# Sonde.net
KiCad netlist of a schematic drawn in EAGLE
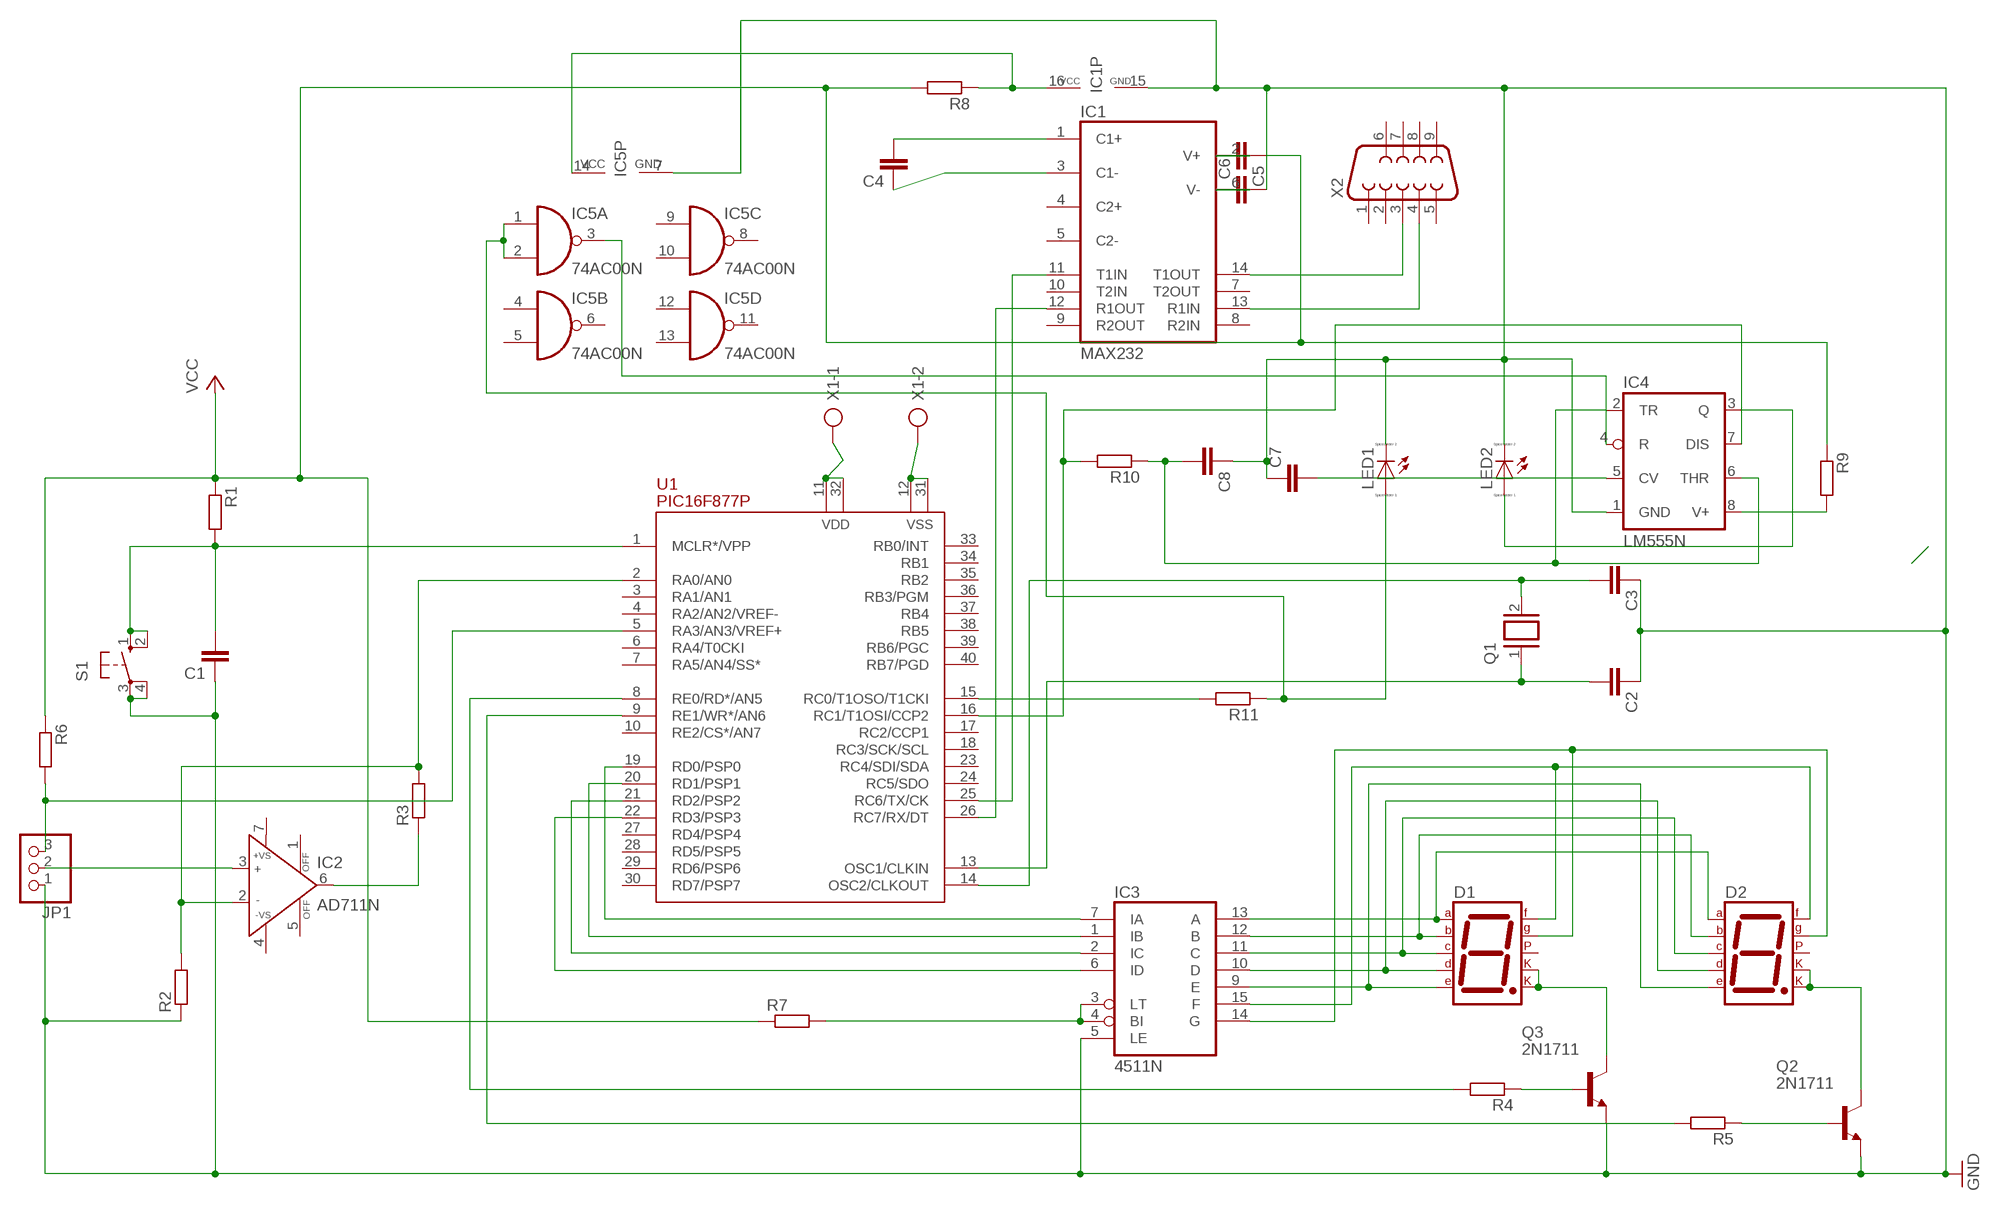
[diagram p0: schematic, sheet 1]

(export (version "E")
  (design (tool "Eeschema 10.0.6"))
  (components
    (comp (ref "C1")
      (value "C-EU025-024X044")
      (footprint "eagle-import:C025-024X044")
      (libsource (lib "eagle-import") (part "C-EU025-024X044"))
    )
    (comp (ref "C2")
      (value "C-EU025-024X044")
      (footprint "eagle-import:C025-024X044")
      (libsource (lib "eagle-import") (part "C-EU025-024X044"))
    )
    (comp (ref "C3")
      (value "C-EU025-024X044")
      (footprint "eagle-import:C025-024X044")
      (libsource (lib "eagle-import") (part "C-EU025-024X044"))
    )
    (comp (ref "C4")
      (value "C-EU025-024X044")
      (footprint "eagle-import:C025-024X044")
      (libsource (lib "eagle-import") (part "C-EU025-024X044"))
    )
    (comp (ref "C5")
      (value "C-EU025-024X044")
      (footprint "eagle-import:C025-024X044")
      (libsource (lib "eagle-import") (part "C-EU025-024X044"))
    )
    (comp (ref "C6")
      (value "C-EU025-024X044")
      (footprint "eagle-import:C025-024X044")
      (libsource (lib "eagle-import") (part "C-EU025-024X044"))
    )
    (comp (ref "C7")
      (value "C-EU025-024X044")
      (footprint "eagle-import:C025-024X044")
      (libsource (lib "eagle-import") (part "C-EU025-024X044"))
    )
    (comp (ref "C8")
      (value "C-EU025-024X044")
      (footprint "eagle-import:C025-024X044")
      (libsource (lib "eagle-import") (part "C-EU025-024X044"))
    )
    (comp (ref "D1")
      (value "7SEG-CK")
      (footprint "eagle-import:7SEG-13")
      (libsource (lib "eagle-import") (part "7SEG-CK"))
    )
    (comp (ref "D2")
      (value "7SEG-CK")
      (footprint "eagle-import:7SEG-13")
      (libsource (lib "eagle-import") (part "7SEG-CK"))
    )
    (comp (ref "IC1")
      (value "MAX232")
      (footprint "eagle-import:DIL16")
      (fields (field (name "MF") "MAXIM") (field (name "MPN") "MAX232ACPE+"))
      (libsource (lib "eagle-import") (part "MAX232"))
    )
    (comp (ref "IC2")
      (value "AD711N")
      (footprint "eagle-import:DIL08")
      (fields (field (name "MPN") "AD711BQ"))
      (libsource (lib "eagle-import") (part "AD711N"))
    )
    (comp (ref "IC3")
      (value "4511N")
      (footprint "eagle-import:DIL16")
      (libsource (lib "eagle-import") (part "4511N"))
    )
    (comp (ref "IC4")
      (value "LM555N")
      (footprint "eagle-import:DIL08")
      (libsource (lib "eagle-import") (part "555NLM"))
    )
    (comp (ref "IC5")
      (value "74AC00N")
      (footprint "eagle-import:DIL14")
      (libsource (lib "eagle-import") (part "7400NAC"))
    )
    (comp (ref "JP1")
      (value "PINHD-1X3")
      (footprint "eagle-import:1X03")
      (libsource (lib "eagle-import") (part "PINHD-1X3"))
    )
    (comp (ref "LED1")
      (value "LED_ELD260")
      (footprint "eagle-import:LED_LD260")
      (libsource (lib "eagle-import") (part "LED_ELD260"))
    )
    (comp (ref "LED2")
      (value "LED_ELD260")
      (footprint "eagle-import:LED_LD260")
      (libsource (lib "eagle-import") (part "LED_ELD260"))
    )
    (comp (ref "Q1")
      (value "XTAL/S")
      (footprint "eagle-import:QS")
      (libsource (lib "eagle-import") (part "XTAL/S"))
    )
    (comp (ref "Q2")
      (value "2N1711")
      (footprint "eagle-import:TO39")
      (libsource (lib "eagle-import") (part "2N1711"))
    )
    (comp (ref "Q3")
      (value "2N1711")
      (footprint "eagle-import:TO39")
      (libsource (lib "eagle-import") (part "2N1711"))
    )
    (comp (ref "R1")
      (value "R-EU_0207/10")
      (footprint "eagle-import:0207_10")
      (libsource (lib "eagle-import") (part "R-EU_0207/10"))
    )
    (comp (ref "R2")
      (value "R-EU_0207/10")
      (footprint "eagle-import:0207_10")
      (libsource (lib "eagle-import") (part "R-EU_0207/10"))
    )
    (comp (ref "R3")
      (value "R-EU_0207/10")
      (footprint "eagle-import:0207_10")
      (libsource (lib "eagle-import") (part "R-EU_0207/10"))
    )
    (comp (ref "R4")
      (value "R-EU_0207/10")
      (footprint "eagle-import:0207_10")
      (libsource (lib "eagle-import") (part "R-EU_0207/10"))
    )
    (comp (ref "R5")
      (value "R-EU_0207/10")
      (footprint "eagle-import:0207_10")
      (libsource (lib "eagle-import") (part "R-EU_0207/10"))
    )
    (comp (ref "R6")
      (value "R-EU_0207/10")
      (footprint "eagle-import:0207_10")
      (libsource (lib "eagle-import") (part "R-EU_0207/10"))
    )
    (comp (ref "R7")
      (value "R-EU_0207/10")
      (footprint "eagle-import:0207_10")
      (libsource (lib "eagle-import") (part "R-EU_0207/10"))
    )
    (comp (ref "R8")
      (value "R-EU_0207/10")
      (footprint "eagle-import:0207_10")
      (libsource (lib "eagle-import") (part "R-EU_0207/10"))
    )
    (comp (ref "R9")
      (value "R-EU_0207/10")
      (footprint "eagle-import:0207_10")
      (libsource (lib "eagle-import") (part "R-EU_0207/10"))
    )
    (comp (ref "R10")
      (value "R-EU_0207/10")
      (footprint "eagle-import:0207_10")
      (libsource (lib "eagle-import") (part "R-EU_0207/10"))
    )
    (comp (ref "R11")
      (value "R-EU_0207/10")
      (footprint "eagle-import:0207_10")
      (libsource (lib "eagle-import") (part "R-EU_0207/10"))
    )
    (comp (ref "S1")
      (value "10-XX")
      (footprint "eagle-import:B3F-10XX")
      (fields (field (name "MPN") "B3F-1000"))
      (libsource (lib "eagle-import") (part "10-XX"))
    )
    (comp (ref "U1")
      (value "PIC16F877P")
      (footprint "eagle-import:DIL40")
      (libsource (lib "eagle-import") (part "PIC16F877P"))
    )
    (comp (ref "X1")
      (value "AK300/2")
      (footprint "eagle-import:AK300_2")
      (libsource (lib "eagle-import") (part "AK300/2"))
    )
    (comp (ref "X2")
      (value "F09D")
      (footprint "eagle-import:F09D")
      (libsource (lib "eagle-import") (part "F09D"))
    )
  )
  (nets
    (net (code "1") (name "GND") (class "Default")
      (node (ref "C1") (pin "1") (pinfunction "1_1") (pintype "passive"))
      (node (ref "C2") (pin "1") (pinfunction "1_1") (pintype "passive"))
      (node (ref "C3") (pin "1") (pinfunction "1_1") (pintype "passive"))
      (node (ref "C6") (pin "2") (pinfunction "2_2") (pintype "passive"))
      (node (ref "C7") (pin "1") (pinfunction "1_1") (pintype "passive"))
      (node (ref "C8") (pin "1") (pinfunction "1_1") (pintype "passive"))
      (node (ref "IC1") (pin "15") (pinfunction "GND_15") (pintype "power_in"))
      (node (ref "IC3") (pin "5") (pinfunction "LE_5") (pintype "input"))
      (node (ref "IC4") (pin "1") (pinfunction "GND_1") (pintype "power_in"))
      (node (ref "IC5") (pin "7") (pinfunction "GND_7") (pintype "power_in"))
      (node (ref "JP1") (pin "1") (pinfunction "1_1") (pintype "passive"))
      (node (ref "LED1") (pin "K") (pinfunction "C_K") (pintype "passive"))
      (node (ref "LED2") (pin "K") (pinfunction "C_K") (pintype "passive"))
      (node (ref "Q2") (pin "1") (pinfunction "E_1") (pintype "passive"))
      (node (ref "Q3") (pin "1") (pinfunction "E_1") (pintype "passive"))
      (node (ref "R2") (pin "1") (pinfunction "1_1") (pintype "passive"))
      (node (ref "S1") (pin "3") (pinfunction "P_3") (pintype "passive"))
      (node (ref "S1") (pin "4") (pinfunction "P1_4") (pintype "passive"))
    )
    (net (code "2") (name "Net-(D1-A)") (class "Default")
      (node (ref "D1") (pin "7") (pinfunction "A_7") (pintype "passive"))
      (node (ref "D2") (pin "7") (pinfunction "A_7") (pintype "passive"))
      (node (ref "IC3") (pin "13") (pinfunction "A_13") (pintype "output"))
    )
    (net (code "3") (name "Net-(D1-B)") (class "Default")
      (node (ref "D1") (pin "6") (pinfunction "B_6") (pintype "passive"))
      (node (ref "D2") (pin "6") (pinfunction "B_6") (pintype "passive"))
      (node (ref "IC3") (pin "12") (pinfunction "B_12") (pintype "output"))
    )
    (net (code "4") (name "Net-(D1-C)") (class "Default")
      (node (ref "D1") (pin "4") (pinfunction "C_4") (pintype "passive"))
      (node (ref "D2") (pin "4") (pinfunction "C_4") (pintype "passive"))
      (node (ref "IC3") (pin "11") (pinfunction "C_11") (pintype "output"))
    )
    (net (code "5") (name "Net-(D1-CK1)") (class "Default")
      (node (ref "D1") (pin "3") (pinfunction "CK1_3") (pintype "passive"))
      (node (ref "D1") (pin "8") (pinfunction "CK2_8") (pintype "passive"))
      (node (ref "Q3") (pin "3") (pinfunction "C_3") (pintype "passive"))
    )
    (net (code "6") (name "Net-(D1-D)") (class "Default")
      (node (ref "D1") (pin "2") (pinfunction "D_2") (pintype "passive"))
      (node (ref "D2") (pin "2") (pinfunction "D_2") (pintype "passive"))
      (node (ref "IC3") (pin "10") (pinfunction "D_10") (pintype "output"))
    )
    (net (code "7") (name "Net-(D1-E)") (class "Default")
      (node (ref "D1") (pin "1") (pinfunction "E_1") (pintype "passive"))
      (node (ref "D2") (pin "1") (pinfunction "E_1") (pintype "passive"))
      (node (ref "IC3") (pin "9") (pinfunction "E_9") (pintype "output"))
    )
    (net (code "8") (name "Net-(D1-F)") (class "Default")
      (node (ref "D1") (pin "9") (pinfunction "F_9") (pintype "passive"))
      (node (ref "D2") (pin "9") (pinfunction "F_9") (pintype "passive"))
      (node (ref "IC3") (pin "15") (pinfunction "F_15") (pintype "output"))
    )
    (net (code "9") (name "Net-(D1-G)") (class "Default")
      (node (ref "D1") (pin "10") (pinfunction "G_10") (pintype "passive"))
      (node (ref "D2") (pin "10") (pinfunction "G_10") (pintype "passive"))
      (node (ref "IC3") (pin "14") (pinfunction "G_14") (pintype "output"))
    )
    (net (code "10") (name "Net-(D2-CK1)") (class "Default")
      (node (ref "D2") (pin "3") (pinfunction "CK1_3") (pintype "passive"))
      (node (ref "D2") (pin "8") (pinfunction "CK2_8") (pintype "passive"))
      (node (ref "Q2") (pin "3") (pinfunction "C_3") (pintype "passive"))
    )
    (net (code "11") (name "Net-(IC1A-C1+)") (class "Default")
      (node (ref "C4") (pin "2") (pinfunction "2_2") (pintype "passive"))
      (node (ref "IC1") (pin "1") (pinfunction "C1+_1") (pintype "bidirectional"))
    )
    (net (code "12") (name "Net-(IC1A-C1-)") (class "Default")
      (node (ref "C4") (pin "1") (pinfunction "1_1") (pintype "passive"))
      (node (ref "IC1") (pin "3") (pinfunction "C1-_3") (pintype "bidirectional"))
    )
    (net (code "13") (name "Net-(IC1A-R1IN)") (class "Default")
      (node (ref "IC1") (pin "13") (pinfunction "R1IN_13") (pintype "input"))
      (node (ref "X2") (pin "4") (pinfunction "4_4") (pintype "passive"))
    )
    (net (code "14") (name "Net-(IC1A-R1OUT)") (class "Default")
      (node (ref "IC1") (pin "12") (pinfunction "R1OUT_12") (pintype "output"))
      (node (ref "U1") (pin "26") (pinfunction "RC7/RX/DT_26") (pintype "bidirectional"))
    )
    (net (code "15") (name "Net-(IC1A-T1IN)") (class "Default")
      (node (ref "IC1") (pin "11") (pinfunction "T1IN_11") (pintype "input"))
      (node (ref "U1") (pin "25") (pinfunction "RC6/TX/CK_25") (pintype "bidirectional"))
    )
    (net (code "16") (name "Net-(IC1A-T1OUT)") (class "Default")
      (node (ref "IC1") (pin "14") (pinfunction "T1OUT_14") (pintype "output"))
      (node (ref "X2") (pin "3") (pinfunction "3_3") (pintype "passive"))
    )
    (net (code "17") (name "Net-(IC1A-V+)") (class "Default")
      (node (ref "C5") (pin "2") (pinfunction "2_2") (pintype "passive"))
      (node (ref "IC1") (pin "2") (pinfunction "V+_2") (pintype "bidirectional"))
    )
    (net (code "18") (name "Net-(IC1A-V-)") (class "Default")
      (node (ref "C6") (pin "1") (pinfunction "1_1") (pintype "passive"))
      (node (ref "IC1") (pin "6") (pinfunction "V-_6") (pintype "bidirectional"))
    )
    (net (code "19") (name "Net-(IC1B-VCC)") (class "Default")
      (node (ref "IC1") (pin "16") (pinfunction "VCC_16") (pintype "power_in"))
      (node (ref "IC5") (pin "14") (pinfunction "VCC_14") (pintype "power_in"))
      (node (ref "R8") (pin "1") (pinfunction "1_1") (pintype "passive"))
    )
    (net (code "20") (name "Net-(IC2-IN+)") (class "Default")
      (node (ref "IC2") (pin "3") (pinfunction "IN+_3") (pintype "input"))
      (node (ref "JP1") (pin "2") (pinfunction "2_2") (pintype "passive"))
    )
    (net (code "21") (name "Net-(IC2-IN-)") (class "Default")
      (node (ref "IC2") (pin "2") (pinfunction "IN-_2") (pintype "input"))
      (node (ref "R2") (pin "2") (pinfunction "2_2") (pintype "passive"))
      (node (ref "R3") (pin "2") (pinfunction "2_2") (pintype "passive"))
      (node (ref "U1") (pin "2") (pinfunction "RA0/AN0_2") (pintype "bidirectional"))
    )
    (net (code "22") (name "Net-(IC2-OUT)") (class "Default")
      (node (ref "IC2") (pin "6") (pinfunction "OUT_6") (pintype "output"))
      (node (ref "R3") (pin "1") (pinfunction "1_1") (pintype "passive"))
    )
    (net (code "23") (name "Net-(IC3A-BI)") (class "Default")
      (node (ref "IC3") (pin "3") (pinfunction "LT_3") (pintype "input"))
      (node (ref "IC3") (pin "4") (pinfunction "BI_4") (pintype "input"))
      (node (ref "R7") (pin "2") (pinfunction "2_2") (pintype "passive"))
    )
    (net (code "24") (name "Net-(IC3A-IA)") (class "Default")
      (node (ref "IC3") (pin "7") (pinfunction "IA_7") (pintype "input"))
      (node (ref "U1") (pin "19") (pinfunction "RD0/PSP0_19") (pintype "bidirectional"))
    )
    (net (code "25") (name "Net-(IC3A-IB)") (class "Default")
      (node (ref "IC3") (pin "1") (pinfunction "IB_1") (pintype "input"))
      (node (ref "U1") (pin "20") (pinfunction "RD1/PSP1_20") (pintype "bidirectional"))
    )
    (net (code "26") (name "Net-(IC3A-IC)") (class "Default")
      (node (ref "IC3") (pin "2") (pinfunction "IC_2") (pintype "input"))
      (node (ref "U1") (pin "21") (pinfunction "RD2/PSP2_21") (pintype "bidirectional"))
    )
    (net (code "27") (name "Net-(IC3A-ID)") (class "Default")
      (node (ref "IC3") (pin "6") (pinfunction "ID_6") (pintype "input"))
      (node (ref "U1") (pin "22") (pinfunction "RD3/PSP3_22") (pintype "bidirectional"))
    )
    (net (code "28") (name "Net-(IC4-CV)") (class "Default")
      (node (ref "C7") (pin "2") (pinfunction "2_2") (pintype "passive"))
      (node (ref "IC4") (pin "5") (pinfunction "CV_5") (pintype "input"))
    )
    (net (code "29") (name "Net-(IC4-DIS)") (class "Default")
      (node (ref "IC4") (pin "7") (pinfunction "DIS_7") (pintype "input"))
      (node (ref "R10") (pin "2") (pinfunction "2_2") (pintype "passive"))
      (node (ref "U1") (pin "16") (pinfunction "RC1/T1OSI/CCP2_16") (pintype "bidirectional"))
    )
    (net (code "30") (name "Net-(IC4-Q)") (class "Default")
      (node (ref "IC4") (pin "3") (pinfunction "Q_3") (pintype "output"))
      (node (ref "LED2") (pin "A") (pinfunction "A_A") (pintype "passive"))
    )
    (net (code "31") (name "Net-(IC4-R)") (class "Default")
      (node (ref "IC4") (pin "4") (pinfunction "R_4") (pintype "input"))
      (node (ref "IC5") (pin "3") (pinfunction "O_3") (pintype "output"))
    )
    (net (code "32") (name "Net-(IC4-THR)") (class "Default")
      (node (ref "C8") (pin "2") (pinfunction "2_2") (pintype "passive"))
      (node (ref "IC4") (pin "2") (pinfunction "TR_2") (pintype "input"))
      (node (ref "IC4") (pin "6") (pinfunction "THR_6") (pintype "input"))
      (node (ref "R10") (pin "1") (pinfunction "1_1") (pintype "passive"))
    )
    (net (code "33") (name "Net-(IC4-V+)") (class "Default")
      (node (ref "IC4") (pin "8") (pinfunction "V+_8") (pintype "power_in"))
      (node (ref "R9") (pin "2") (pinfunction "2_2") (pintype "passive"))
    )
    (net (code "34") (name "Net-(IC5A-I0)") (class "Default")
      (node (ref "IC5") (pin "1") (pinfunction "I0_1") (pintype "input"))
      (node (ref "IC5") (pin "2") (pinfunction "I1_2") (pintype "input"))
      (node (ref "LED1") (pin "A") (pinfunction "A_A") (pintype "passive"))
      (node (ref "R11") (pin "1") (pinfunction "1_1") (pintype "passive"))
    )
    (net (code "35") (name "Net-(Q2-B)") (class "Default")
      (node (ref "Q2") (pin "2") (pinfunction "B_2") (pintype "passive"))
      (node (ref "R5") (pin "1") (pinfunction "1_1") (pintype "passive"))
    )
    (net (code "36") (name "Net-(Q3-B)") (class "Default")
      (node (ref "Q3") (pin "2") (pinfunction "B_2") (pintype "passive"))
      (node (ref "R4") (pin "1") (pinfunction "1_1") (pintype "passive"))
    )
    (net (code "37") (name "Net-(S1-S)") (class "Default")
      (node (ref "C1") (pin "2") (pinfunction "2_2") (pintype "passive"))
      (node (ref "R1") (pin "2") (pinfunction "2_2") (pintype "passive"))
      (node (ref "S1") (pin "1") (pinfunction "S_1") (pintype "passive"))
      (node (ref "S1") (pin "2") (pinfunction "S1_2") (pintype "passive"))
      (node (ref "U1") (pin "1") (pinfunction "MCLR*/VPP_1") (pintype "input"))
    )
    (net (code "38") (name "Net-(U1-OSC1{slash}CLKIN)") (class "Default")
      (node (ref "C2") (pin "2") (pinfunction "2_2") (pintype "passive"))
      (node (ref "Q1") (pin "1") (pinfunction "1_1") (pintype "passive"))
      (node (ref "U1") (pin "13") (pinfunction "OSC1/CLKIN_13") (pintype "input"))
    )
    (net (code "39") (name "Net-(U1-OSC2{slash}CLKOUT)") (class "Default")
      (node (ref "C3") (pin "2") (pinfunction "2_2") (pintype "passive"))
      (node (ref "Q1") (pin "2") (pinfunction "2_2") (pintype "passive"))
      (node (ref "U1") (pin "14") (pinfunction "OSC2/CLKOUT_14") (pintype "output"))
    )
    (net (code "40") (name "Net-(U1-RA3{slash}AN3{slash}VREF+)") (class "Default")
      (node (ref "JP1") (pin "3") (pinfunction "3_3") (pintype "passive"))
      (node (ref "R6") (pin "2") (pinfunction "2_2") (pintype "passive"))
      (node (ref "U1") (pin "5") (pinfunction "RA3/AN3/VREF+_5") (pintype "bidirectional"))
    )
    (net (code "41") (name "Net-(U1-RC0{slash}T1OSO{slash}T1CKI)") (class "Default")
      (node (ref "R11") (pin "2") (pinfunction "2_2") (pintype "passive"))
      (node (ref "U1") (pin "15") (pinfunction "RC0/T1OSO/T1CKI_15") (pintype "bidirectional"))
    )
    (net (code "42") (name "Net-(U1-RE0{slash}RD*{slash}AN5)") (class "Default")
      (node (ref "R4") (pin "2") (pinfunction "2_2") (pintype "passive"))
      (node (ref "U1") (pin "8") (pinfunction "RE0/RD*/AN5_8") (pintype "bidirectional"))
    )
    (net (code "43") (name "Net-(U1-RE1{slash}WR*{slash}AN6)") (class "Default")
      (node (ref "R5") (pin "2") (pinfunction "2_2") (pintype "passive"))
      (node (ref "U1") (pin "9") (pinfunction "RE1/WR*/AN6_9") (pintype "bidirectional"))
    )
    (net (code "44") (name "Net-(X1A-KL)") (class "Default")
      (node (ref "U1") (pin "11") (pinfunction "VDD_11") (pintype "bidirectional"))
      (node (ref "U1") (pin "32") (pinfunction "VDD_32") (pintype "bidirectional"))
      (node (ref "X1") (pin "1") (pinfunction "KL_1") (pintype "passive"))
    )
    (net (code "45") (name "Net-(X1B-KL)") (class "Default")
      (node (ref "U1") (pin "12") (pinfunction "VSS_12") (pintype "bidirectional"))
      (node (ref "U1") (pin "31") (pinfunction "VSS_31") (pintype "bidirectional"))
      (node (ref "X1") (pin "2") (pinfunction "KL_2") (pintype "passive"))
    )
    (net (code "46") (name "VCC") (class "Default")
      (node (ref "C5") (pin "1") (pinfunction "1_1") (pintype "passive"))
      (node (ref "R1") (pin "1") (pinfunction "1_1") (pintype "passive"))
      (node (ref "R6") (pin "1") (pinfunction "1_1") (pintype "passive"))
      (node (ref "R7") (pin "1") (pinfunction "1_1") (pintype "passive"))
      (node (ref "R8") (pin "2") (pinfunction "2_2") (pintype "passive"))
      (node (ref "R9") (pin "1") (pinfunction "1_1") (pintype "passive"))
    )
    (net (code "47") (name "unconnected-(D1-DP-Pad5)") (class "Default")
      (node (ref "D1") (pin "5") (pinfunction "DP_5") (pintype "passive"))
    )
    (net (code "48") (name "unconnected-(D2-DP-Pad5)") (class "Default")
      (node (ref "D2") (pin "5") (pinfunction "DP_5") (pintype "passive"))
    )
    (net (code "49") (name "unconnected-(IC1A-C2+-Pad4)") (class "Default")
      (node (ref "IC1") (pin "4") (pinfunction "C2+_4") (pintype "bidirectional"))
    )
    (net (code "50") (name "unconnected-(IC1A-C2--Pad5)") (class "Default")
      (node (ref "IC1") (pin "5") (pinfunction "C2-_5") (pintype "bidirectional"))
    )
    (net (code "51") (name "unconnected-(IC1A-R2IN-Pad8)") (class "Default")
      (node (ref "IC1") (pin "8") (pinfunction "R2IN_8") (pintype "input"))
    )
    (net (code "52") (name "unconnected-(IC1A-R2OUT-Pad9)") (class "Default")
      (node (ref "IC1") (pin "9") (pinfunction "R2OUT_9") (pintype "output"))
    )
    (net (code "53") (name "unconnected-(IC1A-T2IN-Pad10)") (class "Default")
      (node (ref "IC1") (pin "10") (pinfunction "T2IN_10") (pintype "input"))
    )
    (net (code "54") (name "unconnected-(IC1A-T2OUT-Pad7)") (class "Default")
      (node (ref "IC1") (pin "7") (pinfunction "T2OUT_7") (pintype "output"))
    )
    (net (code "55") (name "unconnected-(IC2-+VS-Pad7)") (class "Default")
      (node (ref "IC2") (pin "7") (pinfunction "+VS_7") (pintype "input"))
    )
    (net (code "56") (name "unconnected-(IC2--VS-Pad4)") (class "Default")
      (node (ref "IC2") (pin "4") (pinfunction "-VS_4") (pintype "input"))
    )
    (net (code "57") (name "unconnected-(IC2-OFF-Pad1)") (class "Default")
      (node (ref "IC2") (pin "1") (pinfunction "OFF_1") (pintype "passive"))
    )
    (net (code "58") (name "unconnected-(IC2-OFF-Pad5)") (class "Default")
      (node (ref "IC2") (pin "5") (pinfunction "OFF_5") (pintype "passive"))
    )
    (net (code "59") (name "unconnected-(IC5B-I0-Pad4)") (class "Default")
      (node (ref "IC5") (pin "4") (pinfunction "I0_4") (pintype "input"))
    )
    (net (code "60") (name "unconnected-(IC5B-I1-Pad5)") (class "Default")
      (node (ref "IC5") (pin "5") (pinfunction "I1_5") (pintype "input"))
    )
    (net (code "61") (name "unconnected-(IC5B-O-Pad6)") (class "Default")
      (node (ref "IC5") (pin "6") (pinfunction "O_6") (pintype "output"))
    )
    (net (code "62") (name "unconnected-(IC5C-I0-Pad9)") (class "Default")
      (node (ref "IC5") (pin "9") (pinfunction "I0_9") (pintype "input"))
    )
    (net (code "63") (name "unconnected-(IC5C-I1-Pad10)") (class "Default")
      (node (ref "IC5") (pin "10") (pinfunction "I1_10") (pintype "input"))
    )
    (net (code "64") (name "unconnected-(IC5C-O-Pad8)") (class "Default")
      (node (ref "IC5") (pin "8") (pinfunction "O_8") (pintype "output"))
    )
    (net (code "65") (name "unconnected-(IC5D-I0-Pad12)") (class "Default")
      (node (ref "IC5") (pin "12") (pinfunction "I0_12") (pintype "input"))
    )
    (net (code "66") (name "unconnected-(IC5D-I1-Pad13)") (class "Default")
      (node (ref "IC5") (pin "13") (pinfunction "I1_13") (pintype "input"))
    )
    (net (code "67") (name "unconnected-(IC5D-O-Pad11)") (class "Default")
      (node (ref "IC5") (pin "11") (pinfunction "O_11") (pintype "output"))
    )
    (net (code "68") (name "unconnected-(U1-RA1{slash}AN1-Pad3)") (class "Default")
      (node (ref "U1") (pin "3") (pinfunction "RA1/AN1_3") (pintype "bidirectional"))
    )
    (net (code "69") (name "unconnected-(U1-RA2{slash}AN2{slash}VREF--Pad4)") (class "Default")
      (node (ref "U1") (pin "4") (pinfunction "RA2/AN2/VREF-_4") (pintype "bidirectional"))
    )
    (net (code "70") (name "unconnected-(U1-RA4{slash}T0CKI-Pad6)") (class "Default")
      (node (ref "U1") (pin "6") (pinfunction "RA4/T0CKI_6") (pintype "bidirectional"))
    )
    (net (code "71") (name "unconnected-(U1-RA5{slash}AN4{slash}SS*-Pad7)") (class "Default")
      (node (ref "U1") (pin "7") (pinfunction "RA5/AN4/SS*_7") (pintype "bidirectional"))
    )
    (net (code "72") (name "unconnected-(U1-RB0{slash}INT-Pad33)") (class "Default")
      (node (ref "U1") (pin "33") (pinfunction "RB0/INT_33") (pintype "bidirectional"))
    )
    (net (code "73") (name "unconnected-(U1-RB1-Pad34)") (class "Default")
      (node (ref "U1") (pin "34") (pinfunction "RB1_34") (pintype "bidirectional"))
    )
    (net (code "74") (name "unconnected-(U1-RB2-Pad35)") (class "Default")
      (node (ref "U1") (pin "35") (pinfunction "RB2_35") (pintype "bidirectional"))
    )
    (net (code "75") (name "unconnected-(U1-RB3{slash}PGM-Pad36)") (class "Default")
      (node (ref "U1") (pin "36") (pinfunction "RB3/PGM_36") (pintype "bidirectional"))
    )
    (net (code "76") (name "unconnected-(U1-RB4-Pad37)") (class "Default")
      (node (ref "U1") (pin "37") (pinfunction "RB4_37") (pintype "bidirectional"))
    )
    (net (code "77") (name "unconnected-(U1-RB5-Pad38)") (class "Default")
      (node (ref "U1") (pin "38") (pinfunction "RB5_38") (pintype "bidirectional"))
    )
    (net (code "78") (name "unconnected-(U1-RB6{slash}PGC-Pad39)") (class "Default")
      (node (ref "U1") (pin "39") (pinfunction "RB6/PGC_39") (pintype "bidirectional"))
    )
    (net (code "79") (name "unconnected-(U1-RB7{slash}PGD-Pad40)") (class "Default")
      (node (ref "U1") (pin "40") (pinfunction "RB7/PGD_40") (pintype "bidirectional"))
    )
    (net (code "80") (name "unconnected-(U1-RC2{slash}CCP1-Pad17)") (class "Default")
      (node (ref "U1") (pin "17") (pinfunction "RC2/CCP1_17") (pintype "bidirectional"))
    )
    (net (code "81") (name "unconnected-(U1-RC3{slash}SCK{slash}SCL-Pad18)") (class "Default")
      (node (ref "U1") (pin "18") (pinfunction "RC3/SCK/SCL_18") (pintype "bidirectional"))
    )
    (net (code "82") (name "unconnected-(U1-RC4{slash}SDI{slash}SDA-Pad23)") (class "Default")
      (node (ref "U1") (pin "23") (pinfunction "RC4/SDI/SDA_23") (pintype "bidirectional"))
    )
    (net (code "83") (name "unconnected-(U1-RC5{slash}SDO-Pad24)") (class "Default")
      (node (ref "U1") (pin "24") (pinfunction "RC5/SDO_24") (pintype "bidirectional"))
    )
    (net (code "84") (name "unconnected-(U1-RD4{slash}PSP4-Pad27)") (class "Default")
      (node (ref "U1") (pin "27") (pinfunction "RD4/PSP4_27") (pintype "bidirectional"))
    )
    (net (code "85") (name "unconnected-(U1-RD5{slash}PSP5-Pad28)") (class "Default")
      (node (ref "U1") (pin "28") (pinfunction "RD5/PSP5_28") (pintype "bidirectional"))
    )
    (net (code "86") (name "unconnected-(U1-RD6{slash}PSP6-Pad29)") (class "Default")
      (node (ref "U1") (pin "29") (pinfunction "RD6/PSP6_29") (pintype "bidirectional"))
    )
    (net (code "87") (name "unconnected-(U1-RD7{slash}PSP7-Pad30)") (class "Default")
      (node (ref "U1") (pin "30") (pinfunction "RD7/PSP7_30") (pintype "bidirectional"))
    )
    (net (code "88") (name "unconnected-(U1-RE2{slash}CS*{slash}AN7-Pad10)") (class "Default")
      (node (ref "U1") (pin "10") (pinfunction "RE2/CS*/AN7_10") (pintype "bidirectional"))
    )
    (net (code "89") (name "unconnected-(X2-Pad1)") (class "Default")
      (node (ref "X2") (pin "1") (pinfunction "1_1") (pintype "passive"))
    )
    (net (code "90") (name "unconnected-(X2-Pad2)") (class "Default")
      (node (ref "X2") (pin "2") (pinfunction "2_2") (pintype "passive"))
    )
    (net (code "91") (name "unconnected-(X2-Pad5)") (class "Default")
      (node (ref "X2") (pin "5") (pinfunction "5_5") (pintype "passive"))
    )
    (net (code "92") (name "unconnected-(X2-Pad6)") (class "Default")
      (node (ref "X2") (pin "6") (pinfunction "6_6") (pintype "passive"))
    )
    (net (code "93") (name "unconnected-(X2-Pad7)") (class "Default")
      (node (ref "X2") (pin "7") (pinfunction "7_7") (pintype "passive"))
    )
    (net (code "94") (name "unconnected-(X2-Pad8)") (class "Default")
      (node (ref "X2") (pin "8") (pinfunction "8_8") (pintype "passive"))
    )
    (net (code "95") (name "unconnected-(X2-Pad9)") (class "Default")
      (node (ref "X2") (pin "9") (pinfunction "9_9") (pintype "passive"))
    )
  )
)
